# SCH_csgo-bomb_2023-04-01.net
KiCad netlist of a schematic drawn in EasyEDA
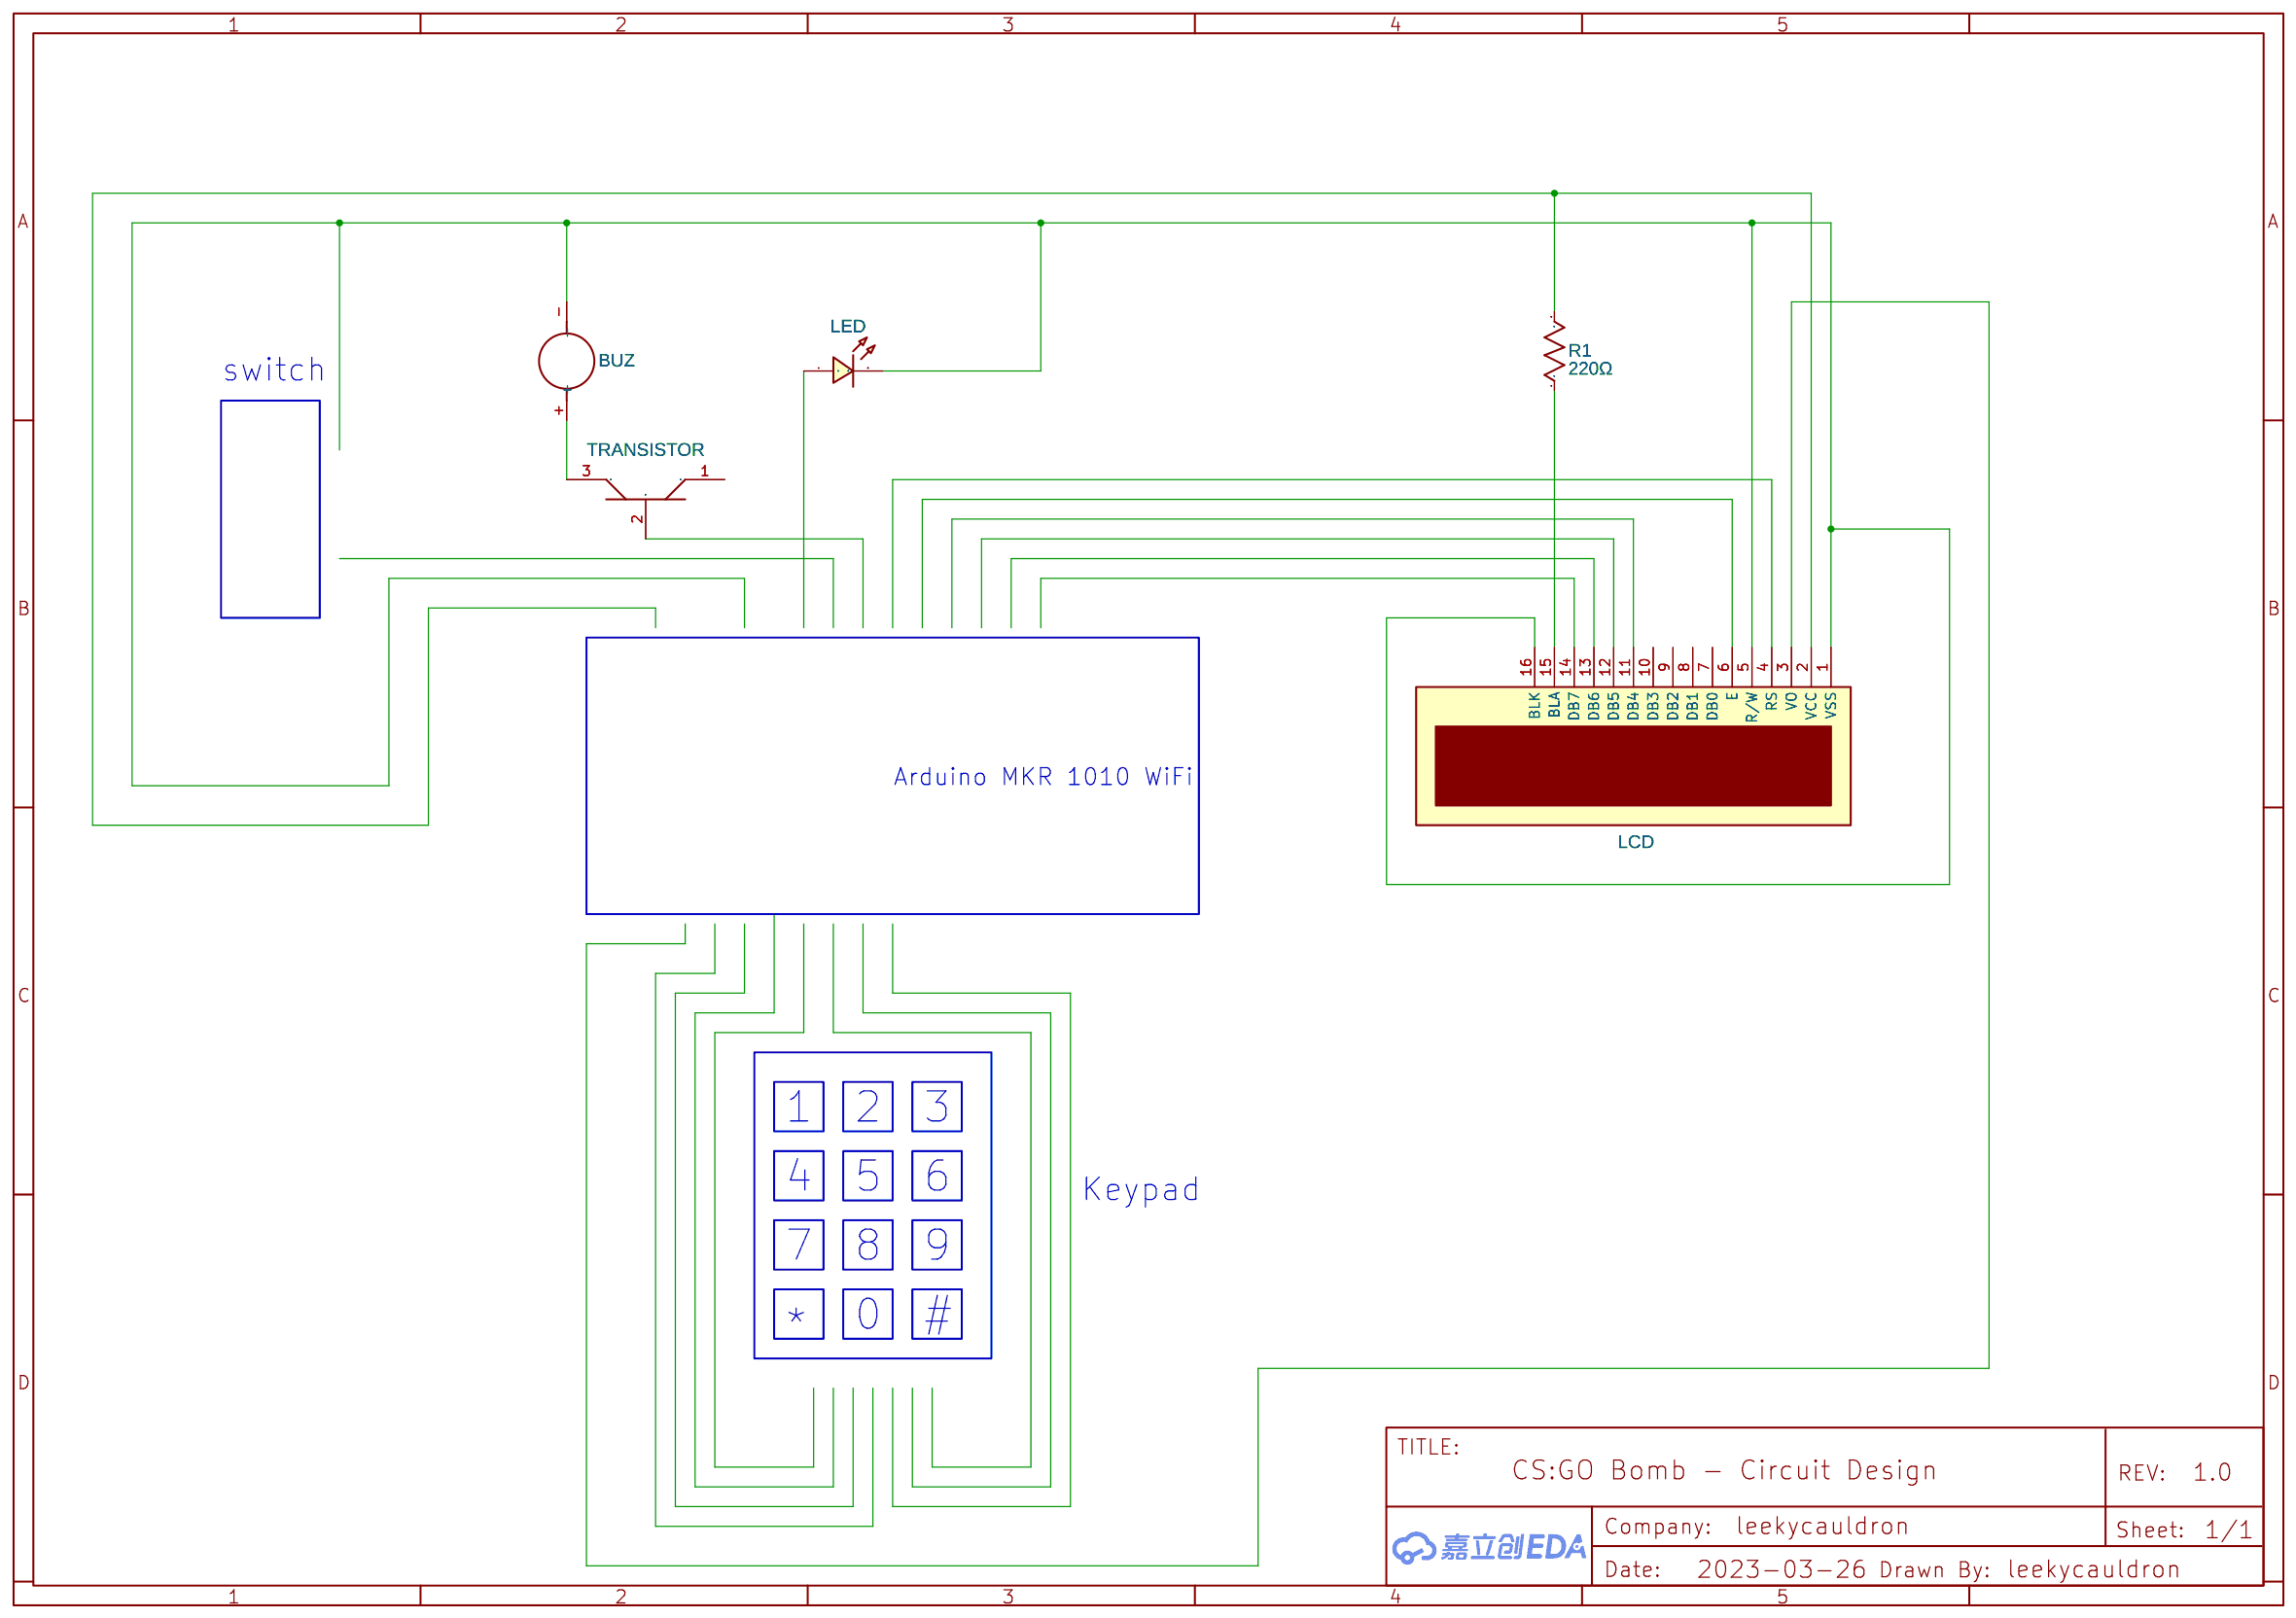
[diagram p0: schematic sheet]

(export (version "E")
  (design (tool "Eeschema 10.0.6"))
  (components
    (comp (ref "BUZ") (value "KS-12065D03YA") (libsource (lib "") (part "KS-12065D03YA")))
    (comp (ref "LCD")
      (value "LCD1602")
      (fields
        (field (name "BOM_Manufacturer Part") "LCM1602K-NSW-BBW")
        (field (name "BOM_Supplier Part") "C83275")
      )
      (libsource (lib "") (part "LCD1602"))
    )
    (comp (ref "LED")
      (value "LED-0603_R")
      (fields
        (field (name "BOM_Manufacturer Part") "19-217/R6C-AL1M2VY/3T")
        (field (name "BOM_Supplier Part") "C72044")
      )
      (libsource (lib "") (part "LED-0603_R"))
    )
    (comp (ref "Q1") (value "TRANSISTOR") (libsource (lib "") (part "TRANSISTOR")))
    (comp (ref "R1") (value "220Ω") (libsource (lib "") (part "R_0603_US")))
  )
  (nets
    (net (code "1") (name "Net-(BUZ-Pad+)") (class "Default")
      (node (ref "BUZ") (pin "+") (pinfunction "+_+") (pintype "unspecified"))
      (node (ref "Q1") (pin "3") (pinfunction "3_3") (pintype "unspecified"))
    )
    (net (code "2") (name "Net-(LCD-BLA)") (class "Default")
      (node (ref "LCD") (pin "15") (pinfunction "BLA_15") (pintype "unspecified"))
      (node (ref "R1") (pin "1") (pinfunction "1_1") (pintype "unspecified"))
    )
    (net (code "3") (name "Net-(LCD-BLK)") (class "Default")
      (node (ref "BUZ") (pin "-") (pinfunction "-_-") (pintype "unspecified"))
      (node (ref "LCD") (pin "1") (pinfunction "VSS_1") (pintype "unspecified"))
      (node (ref "LCD") (pin "16") (pinfunction "BLK_16") (pintype "unspecified"))
      (node (ref "LCD") (pin "5") (pinfunction "R/W_5") (pintype "unspecified"))
      (node (ref "LED") (pin "2") (pinfunction "2_2") (pintype "unspecified"))
    )
    (net (code "4") (name "Net-(LCD-VCC)") (class "Default")
      (node (ref "LCD") (pin "2") (pinfunction "VCC_2") (pintype "unspecified"))
      (node (ref "R1") (pin "2") (pinfunction "2_2") (pintype "unspecified"))
    )
    (net (code "5") (name "unconnected-(LCD-DB0-Pad7)") (class "Default")
      (node (ref "LCD") (pin "7") (pinfunction "DB0_7") (pintype "unspecified"))
    )
    (net (code "6") (name "unconnected-(LCD-DB1-Pad8)") (class "Default")
      (node (ref "LCD") (pin "8") (pinfunction "DB1_8") (pintype "unspecified"))
    )
    (net (code "7") (name "unconnected-(LCD-DB2-Pad9)") (class "Default")
      (node (ref "LCD") (pin "9") (pinfunction "DB2_9") (pintype "unspecified"))
    )
    (net (code "8") (name "unconnected-(LCD-DB3-Pad10)") (class "Default")
      (node (ref "LCD") (pin "10") (pinfunction "DB3_10") (pintype "unspecified"))
    )
    (net (code "9") (name "unconnected-(LCD-DB4-Pad11)") (class "Default")
      (node (ref "LCD") (pin "11") (pinfunction "DB4_11") (pintype "unspecified"))
    )
    (net (code "10") (name "unconnected-(LCD-DB5-Pad12)") (class "Default")
      (node (ref "LCD") (pin "12") (pinfunction "DB5_12") (pintype "unspecified"))
    )
    (net (code "11") (name "unconnected-(LCD-DB6-Pad13)") (class "Default")
      (node (ref "LCD") (pin "13") (pinfunction "DB6_13") (pintype "unspecified"))
    )
    (net (code "12") (name "unconnected-(LCD-DB7-Pad14)") (class "Default")
      (node (ref "LCD") (pin "14") (pinfunction "DB7_14") (pintype "unspecified"))
    )
    (net (code "13") (name "unconnected-(LCD-E-Pad6)") (class "Default")
      (node (ref "LCD") (pin "6") (pinfunction "E_6") (pintype "unspecified"))
    )
    (net (code "14") (name "unconnected-(LCD-RS-Pad4)") (class "Default")
      (node (ref "LCD") (pin "4") (pinfunction "RS_4") (pintype "unspecified"))
    )
    (net (code "15") (name "unconnected-(LCD-VO-Pad3)") (class "Default")
      (node (ref "LCD") (pin "3") (pinfunction "VO_3") (pintype "unspecified"))
    )
    (net (code "16") (name "unconnected-(LED-Pad1)") (class "Default")
      (node (ref "LED") (pin "1") (pinfunction "1_1") (pintype "unspecified"))
    )
    (net (code "17") (name "unconnected-(Q1-Pad1)") (class "Default")
      (node (ref "Q1") (pin "1") (pinfunction "1_1") (pintype "unspecified"))
    )
    (net (code "18") (name "unconnected-(Q1-Pad2)") (class "Default")
      (node (ref "Q1") (pin "2") (pinfunction "2_2") (pintype "unspecified"))
    )
  )
)
